# esp_vectorgame_v1_0.net
KiCad netlist of a schematic drawn in EAGLE
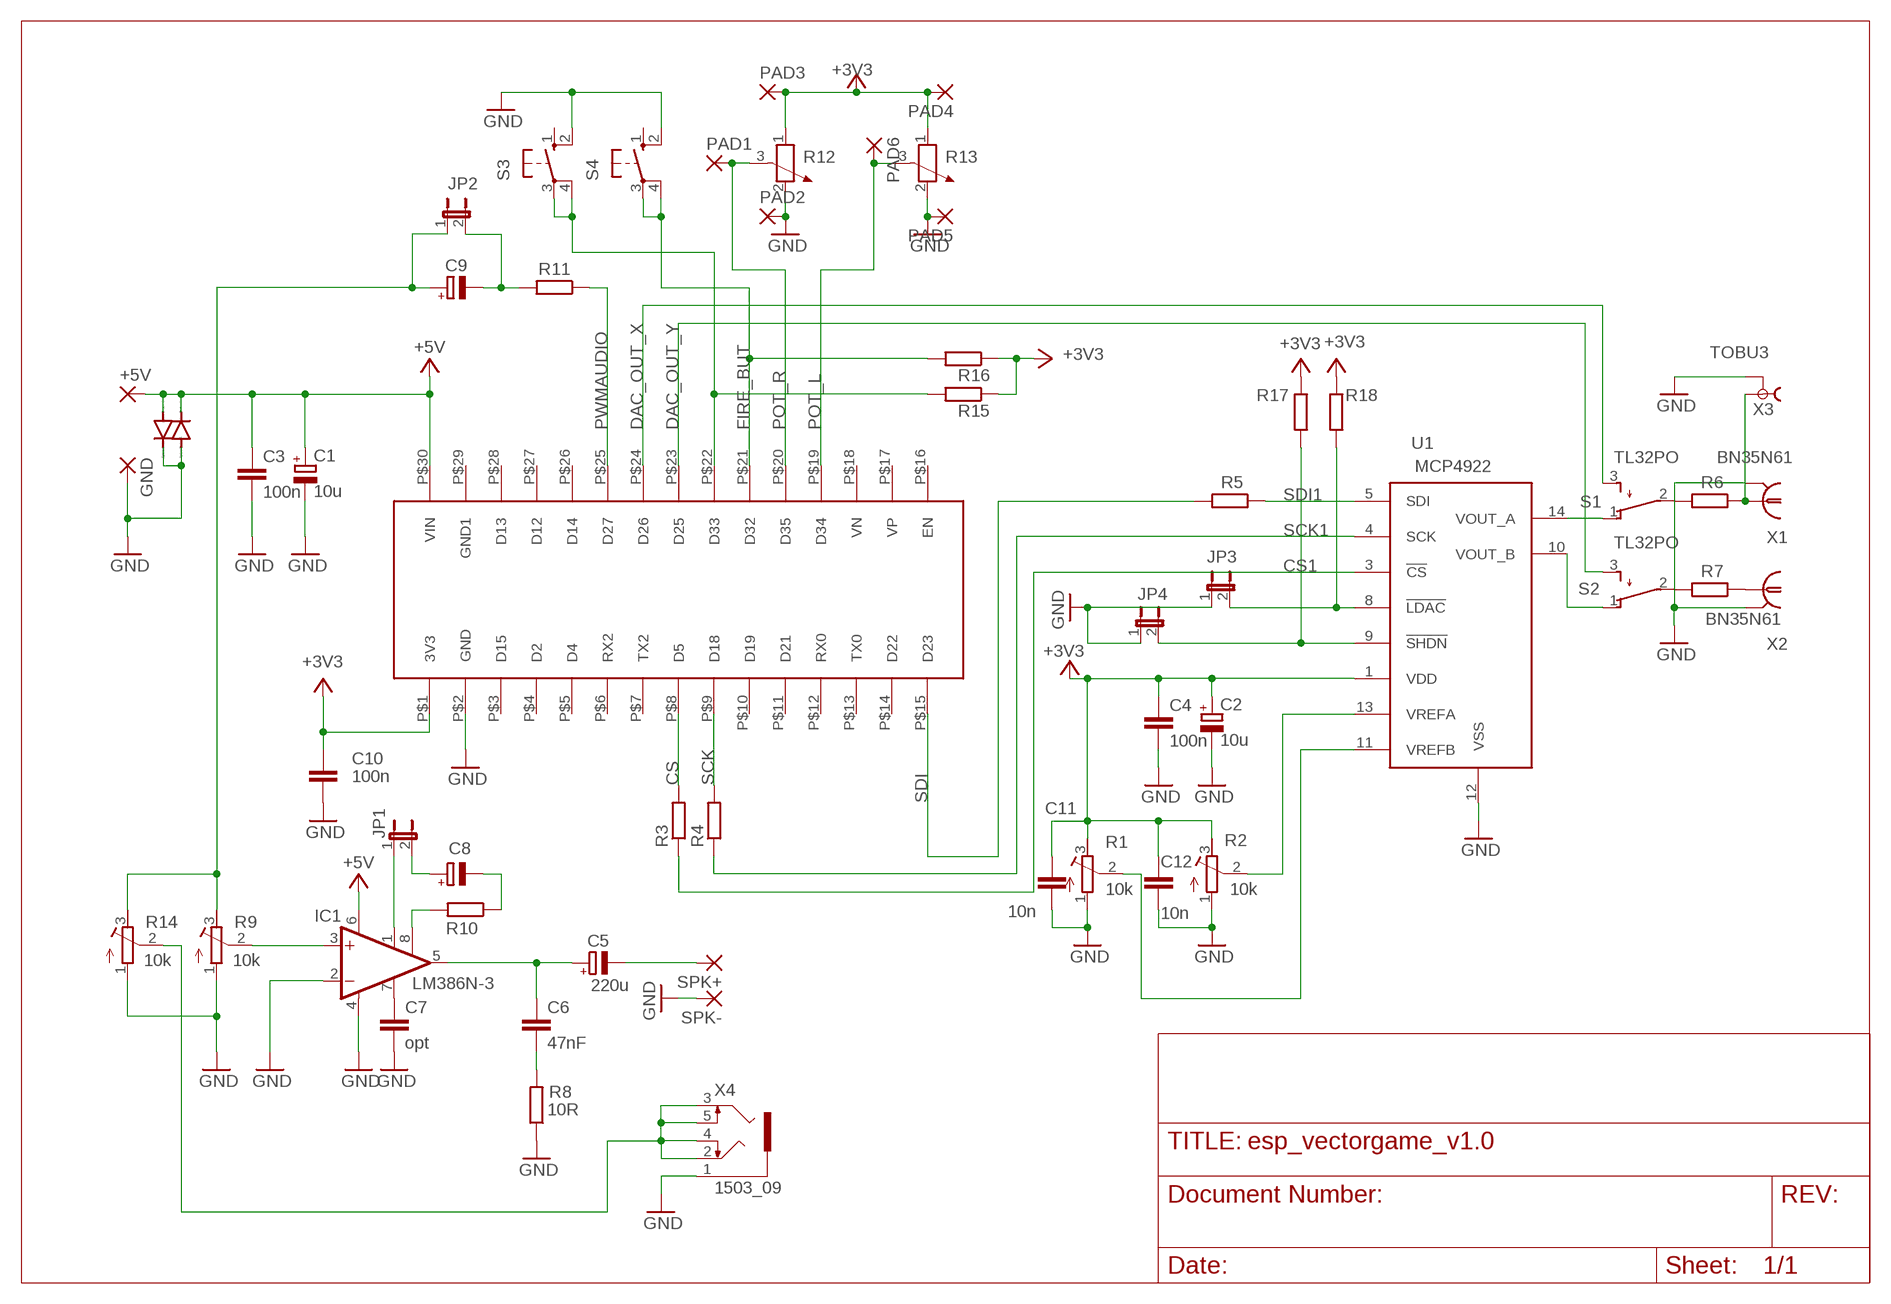
[diagram p0: schematic, sheet 1]

(export (version "E")
  (design (tool "Eeschema 10.0.6"))
  (components
    (comp (ref "+5V")
      (value "3,81/1,4")
      (footprint "eagle-import:3,81_1,4")
      (libsource (lib "eagle-import") (part "3,81/1,4"))
    )
    (comp (ref "C1")
      (value "10u")
      (footprint "eagle-import:E2,5-6E")
      (libsource (lib "eagle-import") (part "CPOL-EUE2,5-6E"))
    )
    (comp (ref "C2")
      (value "10u")
      (footprint "eagle-import:E2,5-6E")
      (libsource (lib "eagle-import") (part "CPOL-EUE2,5-6E"))
    )
    (comp (ref "C3")
      (value "100n")
      (footprint "eagle-import:C0805")
      (libsource (lib "eagle-import") (part "C-EUC0805"))
    )
    (comp (ref "C4")
      (value "100n")
      (footprint "eagle-import:C0805")
      (libsource (lib "eagle-import") (part "C-EUC0805"))
    )
    (comp (ref "C5")
      (value "220u")
      (footprint "eagle-import:E2,5-6E")
      (libsource (lib "eagle-import") (part "CPOL-EUE2,5-6E"))
    )
    (comp (ref "C6")
      (value "47nF")
      (footprint "eagle-import:C0805")
      (libsource (lib "eagle-import") (part "C-EUC0805"))
    )
    (comp (ref "C7")
      (value "opt")
      (footprint "eagle-import:C0805")
      (libsource (lib "eagle-import") (part "C-EUC0805"))
    )
    (comp (ref "C8")
      (value "CPOL-EUE2,5-6E")
      (footprint "eagle-import:E2,5-6E")
      (libsource (lib "eagle-import") (part "CPOL-EUE2,5-6E"))
    )
    (comp (ref "C9")
      (value "CPOL-EUE2,5-6E")
      (footprint "eagle-import:E2,5-6E")
      (libsource (lib "eagle-import") (part "CPOL-EUE2,5-6E"))
    )
    (comp (ref "C10")
      (value "100n")
      (footprint "eagle-import:C0805")
      (libsource (lib "eagle-import") (part "C-EUC0805"))
    )
    (comp (ref "C11")
      (value "10n")
      (footprint "eagle-import:C0805")
      (libsource (lib "eagle-import") (part "C-EUC0805"))
    )
    (comp (ref "C12")
      (value "10n")
      (footprint "eagle-import:C0805")
      (libsource (lib "eagle-import") (part "C-EUC0805"))
    )
    (comp (ref "GND")
      (value "3,81/1,4")
      (footprint "eagle-import:3,81_1,4")
      (libsource (lib "eagle-import") (part "3,81/1,4"))
    )
    (comp (ref "IC1")
      (value "LM386N-3")
      (footprint "eagle-import:DIL08")
      (libsource (lib "eagle-import") (part "LM386?-N3"))
    )
    (comp (ref "JP1")
      (value "JP1E")
      (footprint "eagle-import:JP1")
      (libsource (lib "eagle-import") (part "JP1E"))
    )
    (comp (ref "JP2")
      (value "JP1E")
      (footprint "eagle-import:JP1")
      (libsource (lib "eagle-import") (part "JP1E"))
    )
    (comp (ref "JP3")
      (value "JP1E")
      (footprint "eagle-import:JP1")
      (libsource (lib "eagle-import") (part "JP1E"))
    )
    (comp (ref "JP4")
      (value "JP1E")
      (footprint "eagle-import:JP1")
      (libsource (lib "eagle-import") (part "JP1E"))
    )
    (comp (ref "PAD1")
      (value "3,81/1,4")
      (footprint "eagle-import:3,81_1,4")
      (libsource (lib "eagle-import") (part "3,81/1,4"))
    )
    (comp (ref "PAD2")
      (value "3,81/1,4")
      (footprint "eagle-import:3,81_1,4")
      (libsource (lib "eagle-import") (part "3,81/1,4"))
    )
    (comp (ref "PAD3")
      (value "3,81/1,4")
      (footprint "eagle-import:3,81_1,4")
      (libsource (lib "eagle-import") (part "3,81/1,4"))
    )
    (comp (ref "PAD4")
      (value "3,81/1,4")
      (footprint "eagle-import:3,81_1,4")
      (libsource (lib "eagle-import") (part "3,81/1,4"))
    )
    (comp (ref "PAD5")
      (value "3,81/1,4")
      (footprint "eagle-import:3,81_1,4")
      (libsource (lib "eagle-import") (part "3,81/1,4"))
    )
    (comp (ref "PAD6")
      (value "3,81/1,4")
      (footprint "eagle-import:3,81_1,4")
      (libsource (lib "eagle-import") (part "3,81/1,4"))
    )
    (comp (ref "R1")
      (value "10k")
      (footprint "eagle-import:RTRIM64W")
      (libsource (lib "eagle-import") (part "R-TRIMM64W"))
    )
    (comp (ref "R2")
      (value "10k")
      (footprint "eagle-import:RTRIM64W")
      (libsource (lib "eagle-import") (part "R-TRIMM64W"))
    )
    (comp (ref "R3")
      (value "R-EU_R0805")
      (footprint "eagle-import:R0805")
      (libsource (lib "eagle-import") (part "R-EU_R0805"))
    )
    (comp (ref "R4")
      (value "R-EU_R0805")
      (footprint "eagle-import:R0805")
      (libsource (lib "eagle-import") (part "R-EU_R0805"))
    )
    (comp (ref "R5")
      (value "R-EU_R0805")
      (footprint "eagle-import:R0805")
      (libsource (lib "eagle-import") (part "R-EU_R0805"))
    )
    (comp (ref "R6")
      (value "R-EU_R0805")
      (footprint "eagle-import:R0805")
      (libsource (lib "eagle-import") (part "R-EU_R0805"))
    )
    (comp (ref "R7")
      (value "R-EU_R0805")
      (footprint "eagle-import:R0805")
      (libsource (lib "eagle-import") (part "R-EU_R0805"))
    )
    (comp (ref "R8")
      (value "10R")
      (footprint "eagle-import:R0805")
      (libsource (lib "eagle-import") (part "R-EU_R0805"))
    )
    (comp (ref "R9")
      (value "10k")
      (footprint "eagle-import:RTRIM64W")
      (libsource (lib "eagle-import") (part "R-TRIMM64W"))
    )
    (comp (ref "R10")
      (value "R-EU_R0805")
      (footprint "eagle-import:R0805")
      (libsource (lib "eagle-import") (part "R-EU_R0805"))
    )
    (comp (ref "R11")
      (value "R-EU_R0805")
      (footprint "eagle-import:R0805")
      (libsource (lib "eagle-import") (part "R-EU_R0805"))
    )
    (comp (ref "R12")
      (value "POTENTIOMETER_PT-10")
      (footprint "eagle-import:PT-10")
      (libsource (lib "eagle-import") (part "POTENTIOMETER_PT-10"))
    )
    (comp (ref "R13")
      (value "POTENTIOMETER_PT-10")
      (footprint "eagle-import:PT-10")
      (libsource (lib "eagle-import") (part "POTENTIOMETER_PT-10"))
    )
    (comp (ref "R14")
      (value "10k")
      (footprint "eagle-import:RTRIM64W")
      (libsource (lib "eagle-import") (part "R-TRIMM64W"))
    )
    (comp (ref "R15")
      (value "R-EU_R0805")
      (footprint "eagle-import:R0805")
      (libsource (lib "eagle-import") (part "R-EU_R0805"))
    )
    (comp (ref "R16")
      (value "R-EU_R0805")
      (footprint "eagle-import:R0805")
      (libsource (lib "eagle-import") (part "R-EU_R0805"))
    )
    (comp (ref "R17")
      (value "R-EU_R0805")
      (footprint "eagle-import:R0805")
      (libsource (lib "eagle-import") (part "R-EU_R0805"))
    )
    (comp (ref "R18")
      (value "R-EU_R0805")
      (footprint "eagle-import:R0805")
      (libsource (lib "eagle-import") (part "R-EU_R0805"))
    )
    (comp (ref "S1")
      (value "TL32PO")
      (footprint "eagle-import:TL3XPO")
      (libsource (lib "eagle-import") (part "TL32PO"))
    )
    (comp (ref "S2")
      (value "TL32PO")
      (footprint "eagle-import:TL3XPO")
      (libsource (lib "eagle-import") (part "TL32PO"))
    )
    (comp (ref "S3")
      (value "10-XX")
      (footprint "eagle-import:B3F-10XX")
      (fields (field (name "MPN") "B3F-1000"))
      (libsource (lib "eagle-import") (part "10-XX"))
    )
    (comp (ref "S4")
      (value "10-XX")
      (footprint "eagle-import:B3F-10XX")
      (fields (field (name "MPN") "B3F-1000"))
      (libsource (lib "eagle-import") (part "10-XX"))
    )
    (comp (ref "SPK+")
      (value "3,81/1,4")
      (footprint "eagle-import:3,81_1,4")
      (libsource (lib "eagle-import") (part "3,81/1,4"))
    )
    (comp (ref "SPK-")
      (value "3,81/1,4")
      (footprint "eagle-import:3,81_1,4")
      (libsource (lib "eagle-import") (part "3,81/1,4"))
    )
    (comp (ref "TVS1")
      (value "1N4148DO35-7")
      (footprint "eagle-import:DO35-7")
      (libsource (lib "eagle-import") (part "1N4148DO35-7"))
    )
    (comp (ref "TVS2")
      (value "1N4148DO35-7")
      (footprint "eagle-import:DO35-7")
      (libsource (lib "eagle-import") (part "1N4148DO35-7"))
    )
    (comp (ref "U$2")
      (value "ESP_WROOM32")
      (footprint "eagle-import:ESP_NODEMCU")
      (libsource (lib "eagle-import") (part "ESP_WROOM32"))
    )
    (comp (ref "U1")
      (value "MCP4922")
      (footprint "eagle-import:SO-14")
      (libsource (lib "eagle-import") (part "MCP4922"))
    )
    (comp (ref "X1")
      (value "BN35N61")
      (footprint "eagle-import:B35N61")
      (libsource (lib "eagle-import") (part "BN35N61"))
    )
    (comp (ref "X2")
      (value "BN35N61")
      (footprint "eagle-import:B35N61")
      (libsource (lib "eagle-import") (part "BN35N61"))
    )
    (comp (ref "X3")
      (value "TOBU3")
      (footprint "eagle-import:TOBU3")
      (fields (field (name "MF") "FARNELL") (field (name "MPN") "TOBU 3"))
      (libsource (lib "eagle-import") (part "TOBU3"))
    )
    (comp (ref "X4")
      (value "1503_09")
      (footprint "eagle-import:1503_09")
      (libsource (lib "eagle-import") (part "1503_09"))
    )
  )
  (nets
    (net (code "1") (name "+3V3") (class "Default")
      (node (ref "C10") (pin "1") (pinfunction "1_1") (pintype "passive"))
      (node (ref "C11") (pin "1") (pinfunction "1_1") (pintype "passive"))
      (node (ref "C12") (pin "1") (pinfunction "1_1") (pintype "passive"))
      (node (ref "C2") (pin "+") (pinfunction "+_+") (pintype "passive"))
      (node (ref "C4") (pin "1") (pinfunction "1_1") (pintype "passive"))
      (node (ref "PAD3") (pin "1") (pinfunction "P_1") (pintype "passive"))
      (node (ref "PAD4") (pin "1") (pinfunction "P_1") (pintype "passive"))
      (node (ref "R1") (pin "3") (pinfunction "E_3") (pintype "passive"))
      (node (ref "R12") (pin "1") (pinfunction "1_1") (pintype "passive"))
      (node (ref "R13") (pin "1") (pinfunction "1_1") (pintype "passive"))
      (node (ref "R15") (pin "1") (pinfunction "1_1") (pintype "passive"))
      (node (ref "R16") (pin "1") (pinfunction "1_1") (pintype "passive"))
      (node (ref "R17") (pin "1") (pinfunction "1_1") (pintype "passive"))
      (node (ref "R18") (pin "1") (pinfunction "1_1") (pintype "passive"))
      (node (ref "R2") (pin "3") (pinfunction "E_3") (pintype "passive"))
      (node (ref "U$2") (pin "P$1") (pinfunction "3V3_P$1") (pintype "bidirectional"))
      (node (ref "U1") (pin "1") (pinfunction "VDD_1") (pintype "bidirectional"))
    )
    (net (code "2") (name "+5V") (class "Default")
      (node (ref "+5V") (pin "1") (pinfunction "P_1") (pintype "passive"))
      (node (ref "C1") (pin "+") (pinfunction "+_+") (pintype "passive"))
      (node (ref "C3") (pin "1") (pinfunction "1_1") (pintype "passive"))
      (node (ref "IC1") (pin "6") (pinfunction "VS_6") (pintype "power_in"))
      (node (ref "TVS1") (pin "C") (pinfunction "C_C") (pintype "passive"))
      (node (ref "TVS2") (pin "A") (pinfunction "A_A") (pintype "passive"))
      (node (ref "U$2") (pin "P$30") (pinfunction "VIN_P$30") (pintype "bidirectional"))
    )
    (net (code "3") (name "/CS") (class "Default")
      (node (ref "R3") (pin "2") (pinfunction "2_2") (pintype "passive"))
      (node (ref "U$2") (pin "P$8") (pinfunction "D5_P$8") (pintype "bidirectional"))
    )
    (net (code "4") (name "/CS1") (class "Default")
      (node (ref "R3") (pin "1") (pinfunction "1_1") (pintype "passive"))
      (node (ref "U1") (pin "3") (pinfunction "~{CS}_3") (pintype "bidirectional"))
    )
    (net (code "5") (name "/DAC_OUT_X") (class "Default")
      (node (ref "S1") (pin "3") (pinfunction "S_3") (pintype "passive"))
      (node (ref "U$2") (pin "P$24") (pinfunction "D26_P$24") (pintype "bidirectional"))
    )
    (net (code "6") (name "/DAC_OUT_Y") (class "Default")
      (node (ref "S2") (pin "3") (pinfunction "S_3") (pintype "passive"))
      (node (ref "U$2") (pin "P$23") (pinfunction "D25_P$23") (pintype "bidirectional"))
    )
    (net (code "7") (name "/FIRE_BUT") (class "Default")
      (node (ref "R16") (pin "2") (pinfunction "2_2") (pintype "passive"))
      (node (ref "S4") (pin "3") (pinfunction "P_3") (pintype "passive"))
      (node (ref "S4") (pin "4") (pinfunction "P1_4") (pintype "passive"))
      (node (ref "U$2") (pin "P$21") (pinfunction "D32_P$21") (pintype "bidirectional"))
    )
    (net (code "8") (name "/POT_L") (class "Default")
      (node (ref "PAD6") (pin "1") (pinfunction "P_1") (pintype "passive"))
      (node (ref "R13") (pin "3") (pinfunction "3_3") (pintype "passive"))
      (node (ref "U$2") (pin "P$19") (pinfunction "D34_P$19") (pintype "bidirectional"))
    )
    (net (code "9") (name "/POT_R") (class "Default")
      (node (ref "PAD1") (pin "1") (pinfunction "P_1") (pintype "passive"))
      (node (ref "R12") (pin "3") (pinfunction "3_3") (pintype "passive"))
      (node (ref "U$2") (pin "P$20") (pinfunction "D35_P$20") (pintype "bidirectional"))
    )
    (net (code "10") (name "/PWMAUDIO") (class "Default")
      (node (ref "R11") (pin "1") (pinfunction "1_1") (pintype "passive"))
      (node (ref "U$2") (pin "P$25") (pinfunction "D27_P$25") (pintype "bidirectional"))
    )
    (net (code "11") (name "/SCK") (class "Default")
      (node (ref "R4") (pin "2") (pinfunction "2_2") (pintype "passive"))
      (node (ref "U$2") (pin "P$9") (pinfunction "D18_P$9") (pintype "bidirectional"))
    )
    (net (code "12") (name "/SCK1") (class "Default")
      (node (ref "R4") (pin "1") (pinfunction "1_1") (pintype "passive"))
      (node (ref "U1") (pin "4") (pinfunction "SCK_4") (pintype "bidirectional"))
    )
    (net (code "13") (name "/SDI") (class "Default")
      (node (ref "R5") (pin "2") (pinfunction "2_2") (pintype "passive"))
      (node (ref "U$2") (pin "P$15") (pinfunction "D23_P$15") (pintype "bidirectional"))
    )
    (net (code "14") (name "/SDI1") (class "Default")
      (node (ref "R5") (pin "1") (pinfunction "1_1") (pintype "passive"))
      (node (ref "U1") (pin "5") (pinfunction "SDI_5") (pintype "bidirectional"))
    )
    (net (code "15") (name "GND") (class "Default")
      (node (ref "C1") (pin "-") (pinfunction "-_-") (pintype "passive"))
      (node (ref "C10") (pin "2") (pinfunction "2_2") (pintype "passive"))
      (node (ref "C11") (pin "2") (pinfunction "2_2") (pintype "passive"))
      (node (ref "C12") (pin "2") (pinfunction "2_2") (pintype "passive"))
      (node (ref "C2") (pin "-") (pinfunction "-_-") (pintype "passive"))
      (node (ref "C3") (pin "2") (pinfunction "2_2") (pintype "passive"))
      (node (ref "C4") (pin "2") (pinfunction "2_2") (pintype "passive"))
      (node (ref "C7") (pin "2") (pinfunction "2_2") (pintype "passive"))
      (node (ref "GND") (pin "1") (pinfunction "P_1") (pintype "passive"))
      (node (ref "IC1") (pin "2") (pinfunction "-IN_2") (pintype "input"))
      (node (ref "IC1") (pin "4") (pinfunction "GND_4") (pintype "power_in"))
      (node (ref "JP3") (pin "1") (pinfunction "1_1") (pintype "passive"))
      (node (ref "JP4") (pin "1") (pinfunction "1_1") (pintype "passive"))
      (node (ref "PAD2") (pin "1") (pinfunction "P_1") (pintype "passive"))
      (node (ref "PAD5") (pin "1") (pinfunction "P_1") (pintype "passive"))
      (node (ref "R1") (pin "1") (pinfunction "A_1") (pintype "passive"))
      (node (ref "R12") (pin "2") (pinfunction "2_2") (pintype "passive"))
      (node (ref "R13") (pin "2") (pinfunction "2_2") (pintype "passive"))
      (node (ref "R14") (pin "1") (pinfunction "A_1") (pintype "passive"))
      (node (ref "R2") (pin "1") (pinfunction "A_1") (pintype "passive"))
      (node (ref "R8") (pin "1") (pinfunction "1_1") (pintype "passive"))
      (node (ref "R9") (pin "1") (pinfunction "A_1") (pintype "passive"))
      (node (ref "S3") (pin "2") (pinfunction "S1_2") (pintype "passive"))
      (node (ref "S4") (pin "2") (pinfunction "S1_2") (pintype "passive"))
      (node (ref "SPK-") (pin "1") (pinfunction "P_1") (pintype "passive"))
      (node (ref "TVS1") (pin "A") (pinfunction "A_A") (pintype "passive"))
      (node (ref "TVS2") (pin "C") (pinfunction "C_C") (pintype "passive"))
      (node (ref "U$2") (pin "P$2") (pinfunction "GND_P$2") (pintype "bidirectional"))
      (node (ref "U1") (pin "12") (pinfunction "VSS_12") (pintype "bidirectional"))
      (node (ref "X1") (pin "2") (pinfunction "2_2") (pintype "passive"))
      (node (ref "X1") (pin "3") (pinfunction "2_3") (pintype "passive"))
      (node (ref "X1") (pin "4") (pinfunction "2_4") (pintype "passive"))
      (node (ref "X1") (pin "5") (pinfunction "2_5") (pintype "passive"))
      (node (ref "X2") (pin "2") (pinfunction "2_2") (pintype "passive"))
      (node (ref "X2") (pin "3") (pinfunction "2_3") (pintype "passive"))
      (node (ref "X2") (pin "4") (pinfunction "2_4") (pintype "passive"))
      (node (ref "X2") (pin "5") (pinfunction "2_5") (pintype "passive"))
      (node (ref "X3") (pin "2") (pinfunction "2_2") (pintype "passive"))
      (node (ref "X3") (pin "2@1") (pinfunction "2_2@1") (pintype "passive"))
      (node (ref "X3") (pin "2@2") (pinfunction "2_2@2") (pintype "passive"))
      (node (ref "X4") (pin "1") (pinfunction "1_1") (pintype "passive"))
    )
    (net (code "16") (name "Net-(C6-Pad2)") (class "Default")
      (node (ref "C6") (pin "2") (pinfunction "2_2") (pintype "passive"))
      (node (ref "R8") (pin "2") (pinfunction "2_2") (pintype "passive"))
    )
    (net (code "17") (name "Net-(C8-Pad+)") (class "Default")
      (node (ref "C8") (pin "+") (pinfunction "+_+") (pintype "passive"))
      (node (ref "JP1") (pin "2") (pinfunction "2_2") (pintype "passive"))
    )
    (net (code "18") (name "Net-(C8-Pad-)") (class "Default")
      (node (ref "C8") (pin "-") (pinfunction "-_-") (pintype "passive"))
      (node (ref "R10") (pin "1") (pinfunction "1_1") (pintype "passive"))
    )
    (net (code "19") (name "Net-(C9-Pad-)") (class "Default")
      (node (ref "C9") (pin "-") (pinfunction "-_-") (pintype "passive"))
      (node (ref "JP2") (pin "2") (pinfunction "2_2") (pintype "passive"))
      (node (ref "R11") (pin "2") (pinfunction "2_2") (pintype "passive"))
    )
    (net (code "20") (name "Net-(IC1-+IN)") (class "Default")
      (node (ref "IC1") (pin "3") (pinfunction "+IN_3") (pintype "input"))
      (node (ref "R9") (pin "2") (pinfunction "S_2") (pintype "passive"))
    )
    (net (code "21") (name "Net-(IC1-BYPASS)") (class "Default")
      (node (ref "C7") (pin "1") (pinfunction "1_1") (pintype "passive"))
      (node (ref "IC1") (pin "7") (pinfunction "BYPASS_7") (pintype "passive"))
    )
    (net (code "22") (name "Net-(IC1-GAIN-Pad1)") (class "Default")
      (node (ref "IC1") (pin "1") (pinfunction "GAIN_1") (pintype "passive"))
      (node (ref "JP1") (pin "1") (pinfunction "1_1") (pintype "passive"))
    )
    (net (code "23") (name "Net-(IC1-GAIN-Pad8)") (class "Default")
      (node (ref "IC1") (pin "8") (pinfunction "GAIN_8") (pintype "passive"))
      (node (ref "R10") (pin "2") (pinfunction "2_2") (pintype "passive"))
    )
    (net (code "24") (name "Net-(IC1-OUT)") (class "Default")
      (node (ref "C5") (pin "+") (pinfunction "+_+") (pintype "passive"))
      (node (ref "C6") (pin "1") (pinfunction "1_1") (pintype "passive"))
      (node (ref "IC1") (pin "5") (pinfunction "OUT_5") (pintype "output"))
    )
    (net (code "25") (name "Net-(R1-S)") (class "Default")
      (node (ref "R1") (pin "2") (pinfunction "S_2") (pintype "passive"))
      (node (ref "U1") (pin "11") (pinfunction "VREFB_11") (pintype "bidirectional"))
    )
    (net (code "26") (name "Net-(R2-S)") (class "Default")
      (node (ref "R2") (pin "2") (pinfunction "S_2") (pintype "passive"))
      (node (ref "U1") (pin "13") (pinfunction "VREFA_13") (pintype "bidirectional"))
    )
    (net (code "27") (name "Net-(R6-Pad1)") (class "Default")
      (node (ref "R6") (pin "1") (pinfunction "1_1") (pintype "passive"))
      (node (ref "X1") (pin "1") (pinfunction "1_1") (pintype "passive"))
      (node (ref "X3") (pin "1") (pinfunction "1_1") (pintype "passive"))
    )
    (net (code "28") (name "Net-(R7-Pad1)") (class "Default")
      (node (ref "R7") (pin "1") (pinfunction "1_1") (pintype "passive"))
      (node (ref "X2") (pin "1") (pinfunction "1_1") (pintype "passive"))
    )
    (net (code "29") (name "Net-(R14-E)") (class "Default")
      (node (ref "C9") (pin "+") (pinfunction "+_+") (pintype "passive"))
      (node (ref "JP2") (pin "1") (pinfunction "1_1") (pintype "passive"))
      (node (ref "R14") (pin "3") (pinfunction "E_3") (pintype "passive"))
      (node (ref "R9") (pin "3") (pinfunction "E_3") (pintype "passive"))
    )
    (net (code "30") (name "Net-(R14-S)") (class "Default")
      (node (ref "R14") (pin "2") (pinfunction "S_2") (pintype "passive"))
      (node (ref "X4") (pin "2") (pinfunction "2_2") (pintype "passive"))
      (node (ref "X4") (pin "3") (pinfunction "3_3") (pintype "passive"))
      (node (ref "X4") (pin "4") (pinfunction "4_4") (pintype "passive"))
      (node (ref "X4") (pin "5") (pinfunction "5_5") (pintype "passive"))
    )
    (net (code "31") (name "Net-(S1-O)") (class "Default")
      (node (ref "S1") (pin "1") (pinfunction "O_1") (pintype "passive"))
      (node (ref "U1") (pin "14") (pinfunction "VOUT_A_14") (pintype "bidirectional"))
    )
    (net (code "32") (name "Net-(S1-P)") (class "Default")
      (node (ref "R6") (pin "2") (pinfunction "2_2") (pintype "passive"))
      (node (ref "S1") (pin "2") (pinfunction "P_2") (pintype "passive"))
    )
    (net (code "33") (name "Net-(S2-O)") (class "Default")
      (node (ref "S2") (pin "1") (pinfunction "O_1") (pintype "passive"))
      (node (ref "U1") (pin "10") (pinfunction "VOUT_B_10") (pintype "bidirectional"))
    )
    (net (code "34") (name "Net-(S2-P)") (class "Default")
      (node (ref "R7") (pin "2") (pinfunction "2_2") (pintype "passive"))
      (node (ref "S2") (pin "2") (pinfunction "P_2") (pintype "passive"))
    )
    (net (code "35") (name "Net-(S3-P)") (class "Default")
      (node (ref "R15") (pin "2") (pinfunction "2_2") (pintype "passive"))
      (node (ref "S3") (pin "3") (pinfunction "P_3") (pintype "passive"))
      (node (ref "S3") (pin "4") (pinfunction "P1_4") (pintype "passive"))
      (node (ref "U$2") (pin "P$22") (pinfunction "D33_P$22") (pintype "bidirectional"))
    )
    (net (code "36") (name "Net-(SPK+-P)") (class "Default")
      (node (ref "C5") (pin "-") (pinfunction "-_-") (pintype "passive"))
      (node (ref "SPK+") (pin "1") (pinfunction "P_1") (pintype "passive"))
    )
    (net (code "37") (name "Net-(U1-~{LDAC})") (class "Default")
      (node (ref "JP3") (pin "2") (pinfunction "2_2") (pintype "passive"))
      (node (ref "R18") (pin "2") (pinfunction "2_2") (pintype "passive"))
      (node (ref "U1") (pin "8") (pinfunction "~{LDAC}_8") (pintype "bidirectional"))
    )
    (net (code "38") (name "Net-(U1-~{SHDN})") (class "Default")
      (node (ref "JP4") (pin "2") (pinfunction "2_2") (pintype "passive"))
      (node (ref "R17") (pin "2") (pinfunction "2_2") (pintype "passive"))
      (node (ref "U1") (pin "9") (pinfunction "~{SHDN}_9") (pintype "bidirectional"))
    )
    (net (code "39") (name "unconnected-(S3-S-Pad1)") (class "Default")
      (node (ref "S3") (pin "1") (pinfunction "S_1") (pintype "passive"))
    )
    (net (code "40") (name "unconnected-(S4-S-Pad1)") (class "Default")
      (node (ref "S4") (pin "1") (pinfunction "S_1") (pintype "passive"))
    )
    (net (code "41") (name "unconnected-(U$2-D2-PadP$4)") (class "Default")
      (node (ref "U$2") (pin "P$4") (pinfunction "D2_P$4") (pintype "bidirectional"))
    )
    (net (code "42") (name "unconnected-(U$2-D4-PadP$5)") (class "Default")
      (node (ref "U$2") (pin "P$5") (pinfunction "D4_P$5") (pintype "bidirectional"))
    )
    (net (code "43") (name "unconnected-(U$2-D12-PadP$27)") (class "Default")
      (node (ref "U$2") (pin "P$27") (pinfunction "D12_P$27") (pintype "bidirectional"))
    )
    (net (code "44") (name "unconnected-(U$2-D13-PadP$28)") (class "Default")
      (node (ref "U$2") (pin "P$28") (pinfunction "D13_P$28") (pintype "bidirectional"))
    )
    (net (code "45") (name "unconnected-(U$2-D14-PadP$26)") (class "Default")
      (node (ref "U$2") (pin "P$26") (pinfunction "D14_P$26") (pintype "bidirectional"))
    )
    (net (code "46") (name "unconnected-(U$2-D15-PadP$3)") (class "Default")
      (node (ref "U$2") (pin "P$3") (pinfunction "D15_P$3") (pintype "bidirectional"))
    )
    (net (code "47") (name "unconnected-(U$2-D19-PadP$10)") (class "Default")
      (node (ref "U$2") (pin "P$10") (pinfunction "D19_P$10") (pintype "bidirectional"))
    )
    (net (code "48") (name "unconnected-(U$2-D21-PadP$11)") (class "Default")
      (node (ref "U$2") (pin "P$11") (pinfunction "D21_P$11") (pintype "bidirectional"))
    )
    (net (code "49") (name "unconnected-(U$2-D22-PadP$14)") (class "Default")
      (node (ref "U$2") (pin "P$14") (pinfunction "D22_P$14") (pintype "bidirectional"))
    )
    (net (code "50") (name "unconnected-(U$2-EN-PadP$16)") (class "Default")
      (node (ref "U$2") (pin "P$16") (pinfunction "EN_P$16") (pintype "bidirectional"))
    )
    (net (code "51") (name "unconnected-(U$2-GND1-PadP$29)") (class "Default")
      (node (ref "U$2") (pin "P$29") (pinfunction "GND1_P$29") (pintype "bidirectional"))
    )
    (net (code "52") (name "unconnected-(U$2-RX0-PadP$12)") (class "Default")
      (node (ref "U$2") (pin "P$12") (pinfunction "RX0_P$12") (pintype "bidirectional"))
    )
    (net (code "53") (name "unconnected-(U$2-RX2-PadP$6)") (class "Default")
      (node (ref "U$2") (pin "P$6") (pinfunction "RX2_P$6") (pintype "bidirectional"))
    )
    (net (code "54") (name "unconnected-(U$2-TX0-PadP$13)") (class "Default")
      (node (ref "U$2") (pin "P$13") (pinfunction "TX0_P$13") (pintype "bidirectional"))
    )
    (net (code "55") (name "unconnected-(U$2-TX2-PadP$7)") (class "Default")
      (node (ref "U$2") (pin "P$7") (pinfunction "TX2_P$7") (pintype "bidirectional"))
    )
    (net (code "56") (name "unconnected-(U$2-VN-PadP$18)") (class "Default")
      (node (ref "U$2") (pin "P$18") (pinfunction "VN_P$18") (pintype "bidirectional"))
    )
    (net (code "57") (name "unconnected-(U$2-VP-PadP$17)") (class "Default")
      (node (ref "U$2") (pin "P$17") (pinfunction "VP_P$17") (pintype "bidirectional"))
    )
  )
)
